# Hypnos_V3_1.net
KiCad netlist of a schematic drawn in EAGLE
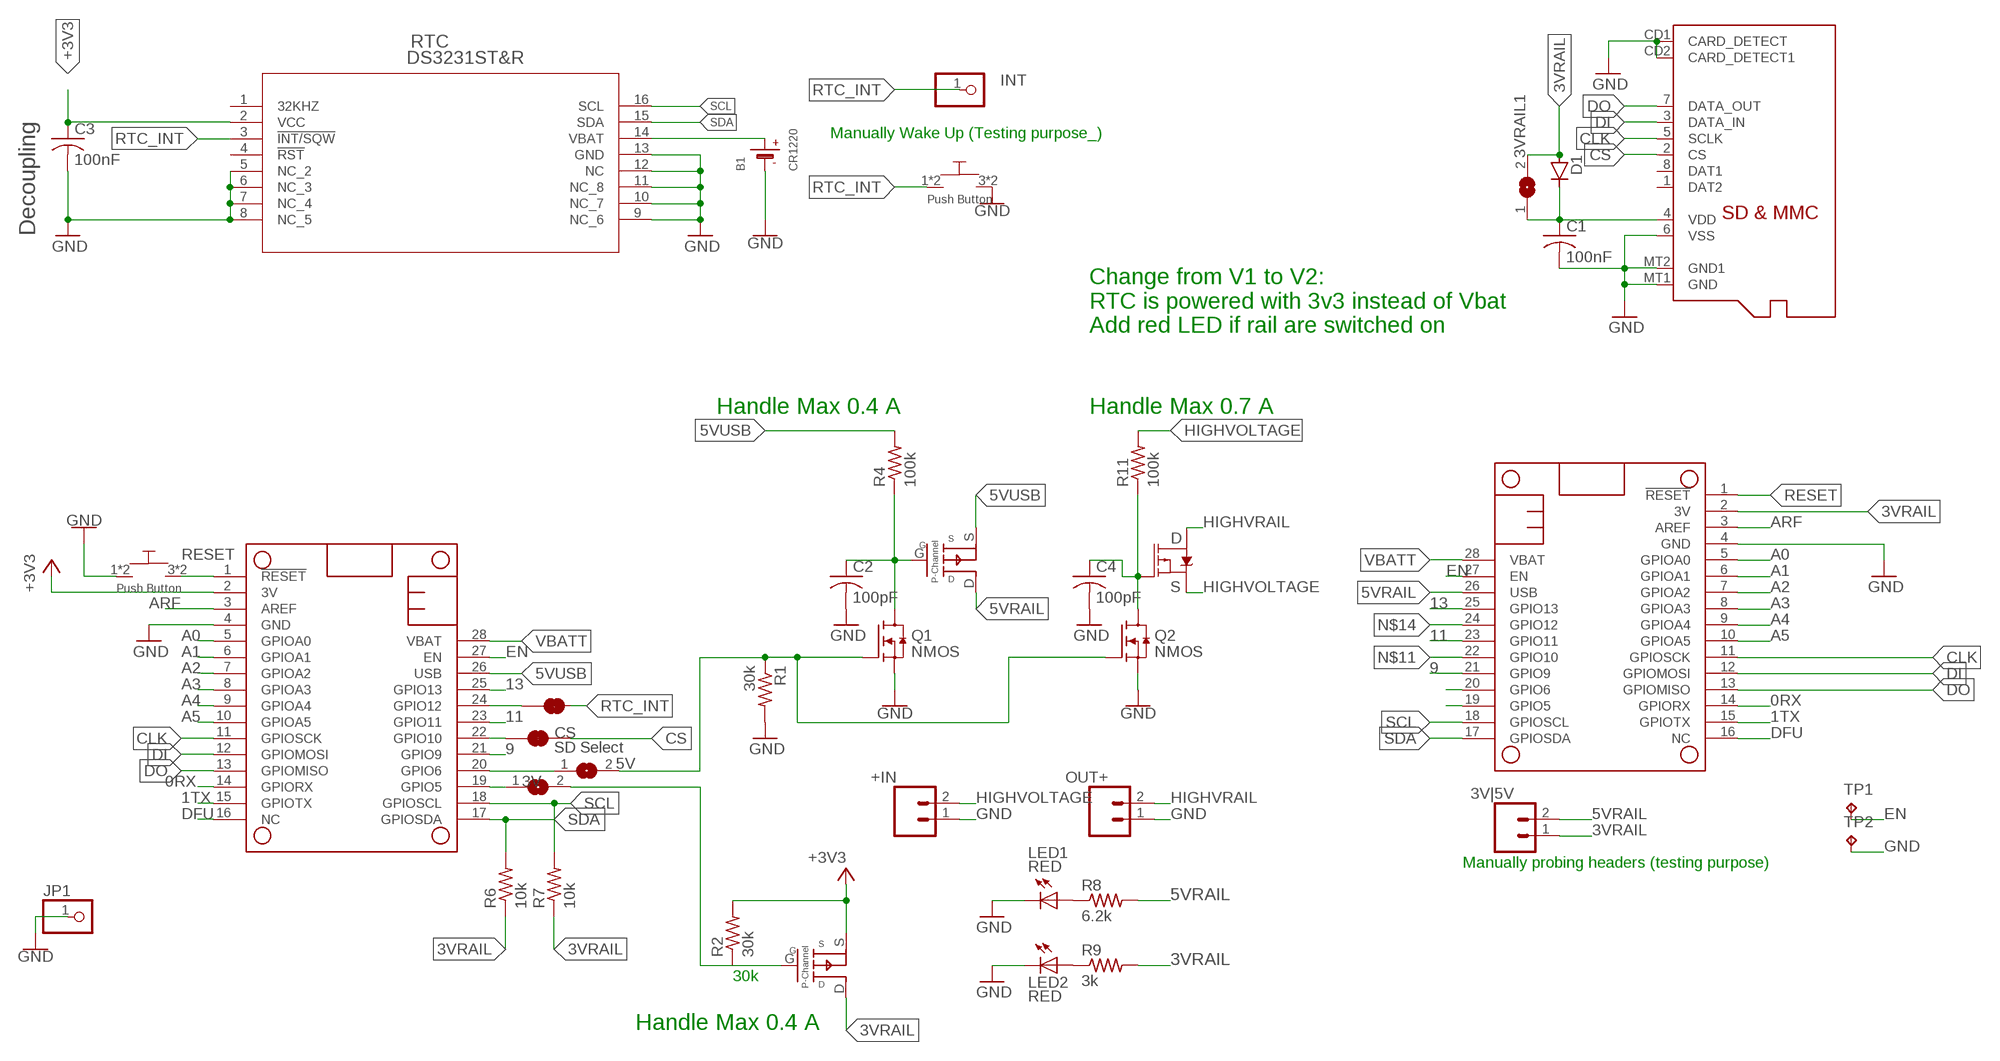
[diagram p0: schematic, sheet 1]

(export (version "E")
  (design (tool "Eeschema 10.0.6"))
  (components
    (comp (ref "+IN")
      (value "HIGHV-IN")
      (footprint "eagle-import:1X02_NO_SILK")
      (libsource (lib "eagle-import") (part "CONN_021X02_NO_SILK"))
    )
    (comp (ref "3V") (value "SJ") (footprint "eagle-import:SJ") (libsource (lib "eagle-import") (part "SJ")))
    (comp (ref "3VRAIL1")
      (value "SJ")
      (footprint "eagle-import:SJ")
      (libsource (lib "eagle-import") (part "SJ"))
    )
    (comp (ref "3V|5V")
      (value "CONN_021X02_NO_SILK")
      (footprint "eagle-import:1X02_NO_SILK")
      (libsource (lib "eagle-import") (part "CONN_021X02_NO_SILK"))
    )
    (comp (ref "5V") (value "SJ") (footprint "eagle-import:SJ") (libsource (lib "eagle-import") (part "SJ")))
    (comp (ref "B1")
      (value "CR1220")
      (footprint "eagle-import:CR1220")
      (libsource (lib "eagle-import") (part "BATTERYCR1220_SMT"))
    )
    (comp (ref "C1")
      (value "100nF")
      (footprint "eagle-import:C1206")
      (libsource (lib "eagle-import") (part "C-USC1206"))
    )
    (comp (ref "C2")
      (value "100pF")
      (footprint "eagle-import:C0805")
      (libsource (lib "eagle-import") (part "resistor_348_C-USC0805"))
    )
    (comp (ref "C3")
      (value "100nF")
      (footprint "eagle-import:C1206")
      (libsource (lib "eagle-import") (part "C-USC1206"))
    )
    (comp (ref "C4")
      (value "100pF")
      (footprint "eagle-import:C0805")
      (libsource (lib "eagle-import") (part "resistor_348_C-USC0805"))
    )
    (comp (ref "CS")
      (value "SD Select")
      (footprint "eagle-import:SMT-JUMPER_2_NC_TRACE_SILK")
      (libsource (lib "eagle-import") (part "JUMPER-SMT_2_NC_TRACE_SILK"))
    )
    (comp (ref "D1")
      (value "D-SOD123")
      (footprint "eagle-import:SOD123")
      (libsource (lib "eagle-import") (part "D-SOD123"))
    )
    (comp (ref "INT")
      (value "PINHD-1X1CB")
      (footprint "eagle-import:1X01-CLEANBIG")
      (libsource (lib "eagle-import") (part "PINHD-1X1CB"))
    )
    (comp (ref "JP1")
      (value "PINHD-1X1CB")
      (footprint "eagle-import:1X01-CLEANBIG")
      (libsource (lib "eagle-import") (part "PINHD-1X1CB"))
    )
    (comp (ref "LED1")
      (value "RED")
      (footprint "eagle-import:CHIPLED_0805")
      (libsource (lib "eagle-import") (part "LEDCHIPLED_0805"))
    )
    (comp (ref "LED2")
      (value "RED")
      (footprint "eagle-import:CHIPLED_0805")
      (libsource (lib "eagle-import") (part "LEDCHIPLED_0805"))
    )
    (comp (ref "MICROSD")
      (value "MICROSD")
      (footprint "eagle-import:MICROSD")
      (libsource (lib "eagle-import") (part "MICROSD"))
    )
    (comp (ref "MS1")
      (value "FEATHERWING")
      (footprint "eagle-import:FEATHERWING")
      (libsource (lib "eagle-import") (part "powerboard_FEATHERWING"))
    )
    (comp (ref "MS2")
      (value "FEATHERWING")
      (footprint "eagle-import:FEATHERWING")
      (libsource (lib "eagle-import") (part "FEATHERWING"))
    )
    (comp (ref "OUT+")
      (value "HIGHV-OUT")
      (footprint "eagle-import:1X02_NO_SILK")
      (libsource (lib "eagle-import") (part "CONN_021X02_NO_SILK"))
    )
    (comp (ref "PMOS1")
      (value "SSM3J3228R")
      (footprint "eagle-import:SOT-23-3")
      (libsource (lib "eagle-import") (part "SSM3J3228R"))
    )
    (comp (ref "PMOS2")
      (value "SSM3J3228R")
      (footprint "eagle-import:SOT-23-3")
      (libsource (lib "eagle-import") (part "SSM3J3228R"))
    )
    (comp (ref "PMOS3")
      (value "P-MOSFET")
      (footprint "eagle-import:SOT23-6")
      (libsource (lib "eagle-import") (part "P-MOSFET"))
    )
    (comp (ref "Q1")
      (value "NMOS")
      (footprint "eagle-import:SOT23-S")
      (libsource (lib "eagle-import") (part "NMOS"))
    )
    (comp (ref "Q2")
      (value "NMOS")
      (footprint "eagle-import:SOT23-S")
      (libsource (lib "eagle-import") (part "NMOS"))
    )
    (comp (ref "R1")
      (value "30k")
      (footprint "eagle-import:RES_1206")
      (fields
        (field (name "DIGIKEY_PART_NUMBER") "WSLP-.05TR-ND")
        (field (name "MANUFACTURER") "Vishay Dale")
        (field (name "MPN") "WSLP1206R0500FEA")
        (field (name "CREATED_BY") "PCBLayout.com")
      )
      (libsource (lib "eagle-import") (part "WSLP1206R0500FEA"))
    )
    (comp (ref "R2")
      (value "30k")
      (footprint "eagle-import:RES_1206")
      (fields
        (field (name "DIGIKEY_PART_NUMBER") "WSLP-.05TR-ND")
        (field (name "MANUFACTURER") "Vishay Dale")
        (field (name "MPN") "WSLP1206R0500FEA")
        (field (name "CREATED_BY") "PCBLayout.com")
      )
      (libsource (lib "eagle-import") (part "WSLP1206R0500FEA"))
    )
    (comp (ref "R4")
      (value "100k")
      (footprint "eagle-import:RES_1206")
      (fields
        (field (name "DIGIKEY_PART_NUMBER") "WSLP-.05TR-ND")
        (field (name "MANUFACTURER") "Vishay Dale")
        (field (name "MPN") "WSLP1206R0500FEA")
        (field (name "CREATED_BY") "PCBLayout.com")
      )
      (libsource (lib "eagle-import") (part "WSLP1206R0500FEA"))
    )
    (comp (ref "R6")
      (value "10k")
      (footprint "eagle-import:RES_1206")
      (fields
        (field (name "DIGIKEY_PART_NUMBER") "WSLP-.05TR-ND")
        (field (name "MANUFACTURER") "Vishay Dale")
        (field (name "MPN") "WSLP1206R0500FEA")
        (field (name "CREATED_BY") "PCBLayout.com")
      )
      (libsource (lib "eagle-import") (part "WSLP1206R0500FEA"))
    )
    (comp (ref "R7")
      (value "10k")
      (footprint "eagle-import:RES_1206")
      (fields
        (field (name "DIGIKEY_PART_NUMBER") "WSLP-.05TR-ND")
        (field (name "MANUFACTURER") "Vishay Dale")
        (field (name "MPN") "WSLP1206R0500FEA")
        (field (name "CREATED_BY") "PCBLayout.com")
      )
      (libsource (lib "eagle-import") (part "WSLP1206R0500FEA"))
    )
    (comp (ref "R8")
      (value "6.2k")
      (footprint "eagle-import:RES_1206")
      (fields
        (field (name "DIGIKEY_PART_NUMBER") "WSLP-.05TR-ND")
        (field (name "MANUFACTURER") "Vishay Dale")
        (field (name "MPN") "WSLP1206R0500FEA")
        (field (name "CREATED_BY") "PCBLayout.com")
      )
      (libsource (lib "eagle-import") (part "WSLP1206R0500FEA"))
    )
    (comp (ref "R9")
      (value "3k")
      (footprint "eagle-import:RES_1206")
      (fields
        (field (name "DIGIKEY_PART_NUMBER") "WSLP-.05TR-ND")
        (field (name "MANUFACTURER") "Vishay Dale")
        (field (name "MPN") "WSLP1206R0500FEA")
        (field (name "CREATED_BY") "PCBLayout.com")
      )
      (libsource (lib "eagle-import") (part "WSLP1206R0500FEA"))
    )
    (comp (ref "R11")
      (value "100k")
      (footprint "eagle-import:RES_1206")
      (fields
        (field (name "DIGIKEY_PART_NUMBER") "WSLP-.05TR-ND")
        (field (name "MANUFACTURER") "Vishay Dale")
        (field (name "MPN") "WSLP1206R0500FEA")
        (field (name "CREATED_BY") "PCBLayout.com")
      )
      (libsource (lib "eagle-import") (part "WSLP1206R0500FEA"))
    )
    (comp (ref "RTC")
      (value "DS3231ST&R")
      (footprint "eagle-import:21-0042B_16")
      (fields (field (name "MANUFACTURER_PART_NUMBER") "DS3231S#T&R"))
      (libsource (lib "eagle-import") (part "DS3231ST&R"))
    )
    (comp (ref "RTC_INT")
      (value "JUMPER-SMT_2_NC_TRACE_SILK")
      (footprint "eagle-import:SMT-JUMPER_2_NC_TRACE_SILK")
      (libsource (lib "eagle-import") (part "JUMPER-SMT_2_NC_TRACE_SILK"))
    )
    (comp (ref "TP1")
      (value "TPTP16R")
      (footprint "eagle-import:TP16R")
      (libsource (lib "eagle-import") (part "TPTP16R"))
    )
    (comp (ref "TP2")
      (value "TPTP16R")
      (footprint "eagle-import:TP16R")
      (libsource (lib "eagle-import") (part "TPTP16R"))
    )
    (comp (ref "U$1")
      (value "PUSH_BUTTON")
      (footprint "eagle-import:PUSHBUTTON_SMD")
      (libsource (lib "eagle-import") (part "PUSH_BUTTON"))
    )
    (comp (ref "U$2")
      (value "PUSH_BUTTON")
      (footprint "eagle-import:PUSHBUTTON_SMD")
      (libsource (lib "eagle-import") (part "PUSH_BUTTON"))
    )
  )
  (nets
    (net (code "1") (name "+3V3") (class "Default")
      (node (ref "C3") (pin "1") (pinfunction "1_1") (pintype "passive"))
      (node (ref "MS2") (pin "2") (pinfunction "3V_2") (pintype "power_in"))
      (node (ref "PMOS2") (pin "S") (pinfunction "S_S") (pintype "bidirectional"))
      (node (ref "R2") (pin "2") (pinfunction "2_2") (pintype "passive"))
      (node (ref "RTC") (pin "2") (pinfunction "VCC_2") (pintype "power_in"))
    )
    (net (code "2") (name "/0RX") (class "Default")
      (node (ref "MS1") (pin "14") (pinfunction "GPIORX_14") (pintype "bidirectional"))
      (node (ref "MS2") (pin "14") (pinfunction "GPIORX_14") (pintype "bidirectional"))
    )
    (net (code "3") (name "/1TX") (class "Default")
      (node (ref "MS1") (pin "15") (pinfunction "GPIOTX_15") (pintype "bidirectional"))
      (node (ref "MS2") (pin "15") (pinfunction "GPIOTX_15") (pintype "bidirectional"))
    )
    (net (code "4") (name "/9") (class "Default")
      (node (ref "MS1") (pin "21") (pinfunction "GPIO9_21") (pintype "bidirectional"))
      (node (ref "MS2") (pin "21") (pinfunction "GPIO9_21") (pintype "bidirectional"))
    )
    (net (code "5") (name "/11") (class "Default")
      (node (ref "MS1") (pin "23") (pinfunction "GPIO11_23") (pintype "bidirectional"))
      (node (ref "MS2") (pin "23") (pinfunction "GPIO11_23") (pintype "bidirectional"))
    )
    (net (code "6") (name "/13") (class "Default")
      (node (ref "MS1") (pin "25") (pinfunction "GPIO13_25") (pintype "bidirectional"))
      (node (ref "MS2") (pin "25") (pinfunction "GPIO13_25") (pintype "bidirectional"))
    )
    (net (code "7") (name "/A0") (class "Default")
      (node (ref "MS1") (pin "5") (pinfunction "GPIOA0_5") (pintype "bidirectional"))
      (node (ref "MS2") (pin "5") (pinfunction "GPIOA0_5") (pintype "bidirectional"))
    )
    (net (code "8") (name "/A1") (class "Default")
      (node (ref "MS1") (pin "6") (pinfunction "GPIOA1_6") (pintype "bidirectional"))
      (node (ref "MS2") (pin "6") (pinfunction "GPIOA1_6") (pintype "bidirectional"))
    )
    (net (code "9") (name "/A2") (class "Default")
      (node (ref "MS1") (pin "7") (pinfunction "GPIOA2_7") (pintype "bidirectional"))
      (node (ref "MS2") (pin "7") (pinfunction "GPIOA2_7") (pintype "bidirectional"))
    )
    (net (code "10") (name "/A3") (class "Default")
      (node (ref "MS1") (pin "8") (pinfunction "GPIOA3_8") (pintype "bidirectional"))
      (node (ref "MS2") (pin "8") (pinfunction "GPIOA3_8") (pintype "bidirectional"))
    )
    (net (code "11") (name "/A4") (class "Default")
      (node (ref "MS1") (pin "9") (pinfunction "GPIOA4_9") (pintype "bidirectional"))
      (node (ref "MS2") (pin "9") (pinfunction "GPIOA4_9") (pintype "bidirectional"))
    )
    (net (code "12") (name "/A5") (class "Default")
      (node (ref "MS1") (pin "10") (pinfunction "GPIOA5_10") (pintype "bidirectional"))
      (node (ref "MS2") (pin "10") (pinfunction "GPIOA5_10") (pintype "bidirectional"))
    )
    (net (code "13") (name "/ARF") (class "Default")
      (node (ref "MS1") (pin "3") (pinfunction "AREF_3") (pintype "passive"))
      (node (ref "MS2") (pin "3") (pinfunction "AREF_3") (pintype "passive"))
    )
    (net (code "14") (name "/DFU") (class "Default")
      (node (ref "MS1") (pin "16") (pinfunction "NC_16") (pintype "passive"))
      (node (ref "MS2") (pin "16") (pinfunction "NC_16") (pintype "passive"))
    )
    (net (code "15") (name "/EN") (class "Default")
      (node (ref "MS1") (pin "27") (pinfunction "EN_27") (pintype "passive"))
      (node (ref "MS2") (pin "27") (pinfunction "EN_27") (pintype "passive"))
      (node (ref "TP1") (pin "TP") (pinfunction "TP_TP") (pintype "input"))
    )
    (net (code "16") (name "/HIGHVRAIL") (class "Default")
      (node (ref "OUT+") (pin "2") (pinfunction "2_2") (pintype "passive"))
      (node (ref "PMOS3") (pin "1") (pinfunction "D_1") (pintype "bidirectional"))
      (node (ref "PMOS3") (pin "2") (pinfunction "D_2") (pintype "bidirectional"))
      (node (ref "PMOS3") (pin "5") (pinfunction "D_5") (pintype "bidirectional"))
      (node (ref "PMOS3") (pin "6") (pinfunction "D_6") (pintype "bidirectional"))
    )
    (net (code "17") (name "3VRAIL") (class "Default")
      (node (ref "3VRAIL1") (pin "2") (pinfunction "2_2") (pintype "passive"))
      (node (ref "3V|5V") (pin "1") (pinfunction "1_1") (pintype "passive"))
      (node (ref "D1") (pin "2") (pinfunction "A_2") (pintype "passive"))
      (node (ref "MS1") (pin "2") (pinfunction "3V_2") (pintype "power_in"))
      (node (ref "PMOS2") (pin "D") (pinfunction "D_D") (pintype "bidirectional"))
      (node (ref "R6") (pin "1") (pinfunction "1_1") (pintype "passive"))
      (node (ref "R7") (pin "1") (pinfunction "1_1") (pintype "passive"))
      (node (ref "R9") (pin "2") (pinfunction "2_2") (pintype "passive"))
    )
    (net (code "18") (name "5VRAIL") (class "Default")
      (node (ref "3V|5V") (pin "2") (pinfunction "2_2") (pintype "passive"))
      (node (ref "MS1") (pin "26") (pinfunction "USB_26") (pintype "power_in"))
      (node (ref "PMOS1") (pin "D") (pinfunction "D_D") (pintype "bidirectional"))
      (node (ref "R8") (pin "2") (pinfunction "2_2") (pintype "passive"))
    )
    (net (code "19") (name "5VUSB") (class "Default")
      (node (ref "MS2") (pin "26") (pinfunction "USB_26") (pintype "power_in"))
      (node (ref "PMOS1") (pin "S") (pinfunction "S_S") (pintype "bidirectional"))
      (node (ref "R4") (pin "2") (pinfunction "2_2") (pintype "passive"))
    )
    (net (code "20") (name "CLK") (class "Default")
      (node (ref "MICROSD") (pin "5") (pinfunction "SCLK_5") (pintype "input"))
      (node (ref "MS1") (pin "11") (pinfunction "GPIOSCK_11") (pintype "bidirectional"))
      (node (ref "MS2") (pin "11") (pinfunction "GPIOSCK_11") (pintype "bidirectional"))
    )
    (net (code "21") (name "CS") (class "Default")
      (node (ref "CS") (pin "2") (pinfunction "2_2") (pintype "passive"))
      (node (ref "MICROSD") (pin "2") (pinfunction "CS_2") (pintype "input"))
    )
    (net (code "22") (name "DI") (class "Default")
      (node (ref "MICROSD") (pin "3") (pinfunction "DATA_IN_3") (pintype "input"))
      (node (ref "MS1") (pin "12") (pinfunction "GPIOMOSI_12") (pintype "bidirectional"))
      (node (ref "MS2") (pin "12") (pinfunction "GPIOMOSI_12") (pintype "bidirectional"))
    )
    (net (code "23") (name "DO") (class "Default")
      (node (ref "MICROSD") (pin "7") (pinfunction "DATA_OUT_7") (pintype "output"))
      (node (ref "MS1") (pin "13") (pinfunction "GPIOMISO_13") (pintype "bidirectional"))
      (node (ref "MS2") (pin "13") (pinfunction "GPIOMISO_13") (pintype "bidirectional"))
    )
    (net (code "24") (name "GND") (class "Default")
      (node (ref "+IN") (pin "1") (pinfunction "1_1") (pintype "passive"))
      (node (ref "B1") (pin "-") (pinfunction "-_-") (pintype "passive"))
      (node (ref "C1") (pin "2") (pinfunction "2_2") (pintype "passive"))
      (node (ref "C2") (pin "2") (pinfunction "2_2") (pintype "passive"))
      (node (ref "C3") (pin "2") (pinfunction "2_2") (pintype "passive"))
      (node (ref "C4") (pin "2") (pinfunction "2_2") (pintype "passive"))
      (node (ref "JP1") (pin "1") (pinfunction "1_1") (pintype "passive"))
      (node (ref "LED1") (pin "C") (pinfunction "C_C") (pintype "passive"))
      (node (ref "LED2") (pin "C") (pinfunction "C_C") (pintype "passive"))
      (node (ref "MICROSD") (pin "6") (pinfunction "VSS_6") (pintype "power_in"))
      (node (ref "MICROSD") (pin "CD1") (pinfunction "CARD_DETECT_CD1") (pintype "passive"))
      (node (ref "MICROSD") (pin "CD2") (pinfunction "CARD_DETECT1_CD2") (pintype "passive"))
      (node (ref "MICROSD") (pin "MT1") (pinfunction "GND_MT1") (pintype "power_in"))
      (node (ref "MICROSD") (pin "MT2") (pinfunction "GND1_MT2") (pintype "power_in"))
      (node (ref "MS1") (pin "4") (pinfunction "GND_4") (pintype "power_in"))
      (node (ref "MS2") (pin "4") (pinfunction "GND_4") (pintype "power_in"))
      (node (ref "OUT+") (pin "1") (pinfunction "1_1") (pintype "passive"))
      (node (ref "Q1") (pin "2") (pinfunction "S_2") (pintype "passive"))
      (node (ref "Q2") (pin "2") (pinfunction "S_2") (pintype "passive"))
      (node (ref "R1") (pin "2") (pinfunction "2_2") (pintype "passive"))
      (node (ref "RTC") (pin "10") (pinfunction "NC_7_10") (pintype "passive"))
      (node (ref "RTC") (pin "11") (pinfunction "NC_8_11") (pintype "passive"))
      (node (ref "RTC") (pin "12") (pinfunction "NC_12") (pintype "passive"))
      (node (ref "RTC") (pin "13") (pinfunction "GND_13") (pintype "power_in"))
      (node (ref "RTC") (pin "5") (pinfunction "NC_2_5") (pintype "passive"))
      (node (ref "RTC") (pin "6") (pinfunction "NC_3_6") (pintype "passive"))
      (node (ref "RTC") (pin "7") (pinfunction "NC_4_7") (pintype "passive"))
      (node (ref "RTC") (pin "8") (pinfunction "NC_5_8") (pintype "passive"))
      (node (ref "RTC") (pin "9") (pinfunction "NC_6_9") (pintype "passive"))
      (node (ref "TP2") (pin "TP") (pinfunction "TP_TP") (pintype "input"))
      (node (ref "U$1") (pin "1") (pinfunction "P$1_1") (pintype "bidirectional"))
      (node (ref "U$1") (pin "2") (pinfunction "P$1_2") (pintype "bidirectional"))
      (node (ref "U$2") (pin "3") (pinfunction "P$2_3") (pintype "bidirectional"))
      (node (ref "U$2") (pin "4") (pinfunction "P$2_4") (pintype "bidirectional"))
    )
    (net (code "25") (name "HIGHVOLTAGE") (class "Default")
      (node (ref "+IN") (pin "2") (pinfunction "2_2") (pintype "passive"))
      (node (ref "PMOS3") (pin "4") (pinfunction "S_4") (pintype "bidirectional"))
      (node (ref "R11") (pin "2") (pinfunction "2_2") (pintype "passive"))
    )
    (net (code "26") (name "N$11") (class "Default")
      (node (ref "CS") (pin "1") (pinfunction "1_1") (pintype "passive"))
      (node (ref "MS1") (pin "22") (pinfunction "GPIO10_22") (pintype "bidirectional"))
      (node (ref "MS2") (pin "22") (pinfunction "GPIO10_22") (pintype "bidirectional"))
    )
    (net (code "27") (name "N$14") (class "Default")
      (node (ref "MS1") (pin "24") (pinfunction "GPIO12_24") (pintype "bidirectional"))
      (node (ref "MS2") (pin "24") (pinfunction "GPIO12_24") (pintype "bidirectional"))
      (node (ref "RTC_INT") (pin "1") (pinfunction "1_1") (pintype "passive"))
    )
    (net (code "28") (name "Net-(3V-Pad2)") (class "Default")
      (node (ref "3V") (pin "2") (pinfunction "2_2") (pintype "passive"))
      (node (ref "PMOS2") (pin "G") (pinfunction "G_G") (pintype "bidirectional"))
      (node (ref "R2") (pin "1") (pinfunction "1_1") (pintype "passive"))
    )
    (net (code "29") (name "Net-(B1-+)") (class "Default")
      (node (ref "B1") (pin "+$1") (pinfunction "+_+$1") (pintype "passive"))
      (node (ref "RTC") (pin "14") (pinfunction "VBAT_14") (pintype "power_in"))
    )
    (net (code "30") (name "Net-(D1-C)") (class "Default")
      (node (ref "3VRAIL1") (pin "1") (pinfunction "1_1") (pintype "passive"))
      (node (ref "C1") (pin "1") (pinfunction "1_1") (pintype "passive"))
      (node (ref "D1") (pin "1") (pinfunction "C_1") (pintype "passive"))
      (node (ref "MICROSD") (pin "4") (pinfunction "VDD_4") (pintype "power_in"))
    )
    (net (code "31") (name "Net-(LED1-PadA)") (class "Default")
      (node (ref "LED1") (pin "A") (pinfunction "A_A") (pintype "passive"))
      (node (ref "R8") (pin "1") (pinfunction "1_1") (pintype "passive"))
    )
    (net (code "32") (name "Net-(LED2-PadA)") (class "Default")
      (node (ref "LED2") (pin "A") (pinfunction "A_A") (pintype "passive"))
      (node (ref "R9") (pin "1") (pinfunction "1_1") (pintype "passive"))
    )
    (net (code "33") (name "Net-(MS2-GPIO5)") (class "Default")
      (node (ref "3V") (pin "1") (pinfunction "1_1") (pintype "passive"))
      (node (ref "MS2") (pin "19") (pinfunction "GPIO5_19") (pintype "bidirectional"))
    )
    (net (code "34") (name "Net-(MS2-GPIO6)") (class "Default")
      (node (ref "5V") (pin "1") (pinfunction "1_1") (pintype "passive"))
      (node (ref "MS2") (pin "20") (pinfunction "GPIO6_20") (pintype "bidirectional"))
    )
    (net (code "35") (name "Net-(PMOS3-G)") (class "Default")
      (node (ref "C4") (pin "1") (pinfunction "1_1") (pintype "passive"))
      (node (ref "PMOS3") (pin "3") (pinfunction "G_3") (pintype "bidirectional"))
      (node (ref "Q2") (pin "3") (pinfunction "D_3") (pintype "passive"))
      (node (ref "R11") (pin "1") (pinfunction "1_1") (pintype "passive"))
    )
    (net (code "36") (name "Net-(Q1-D)") (class "Default")
      (node (ref "C2") (pin "1") (pinfunction "1_1") (pintype "passive"))
      (node (ref "PMOS1") (pin "G") (pinfunction "G_G") (pintype "bidirectional"))
      (node (ref "Q1") (pin "3") (pinfunction "D_3") (pintype "passive"))
      (node (ref "R4") (pin "1") (pinfunction "1_1") (pintype "passive"))
    )
    (net (code "37") (name "Net-(Q1-G)") (class "Default")
      (node (ref "5V") (pin "2") (pinfunction "2_2") (pintype "passive"))
      (node (ref "Q1") (pin "1") (pinfunction "G_1") (pintype "passive"))
      (node (ref "Q2") (pin "1") (pinfunction "G_1") (pintype "passive"))
      (node (ref "R1") (pin "1") (pinfunction "1_1") (pintype "passive"))
    )
    (net (code "38") (name "RESET") (class "Default")
      (node (ref "MS1") (pin "1") (pinfunction "~{RESET}_1") (pintype "input"))
      (node (ref "MS2") (pin "1") (pinfunction "~{RESET}_1") (pintype "input"))
      (node (ref "U$1") (pin "3") (pinfunction "P$2_3") (pintype "bidirectional"))
      (node (ref "U$1") (pin "4") (pinfunction "P$2_4") (pintype "bidirectional"))
    )
    (net (code "39") (name "RTC_INT") (class "Default")
      (node (ref "INT") (pin "1") (pinfunction "1_1") (pintype "passive"))
      (node (ref "RTC") (pin "3") (pinfunction "~{INT/SQW}_3") (pintype "passive"))
      (node (ref "RTC_INT") (pin "2") (pinfunction "2_2") (pintype "passive"))
      (node (ref "U$2") (pin "1") (pinfunction "P$1_1") (pintype "bidirectional"))
      (node (ref "U$2") (pin "2") (pinfunction "P$1_2") (pintype "bidirectional"))
    )
    (net (code "40") (name "SCL") (class "Default")
      (node (ref "MS1") (pin "18") (pinfunction "GPIOSCL_18") (pintype "bidirectional"))
      (node (ref "MS2") (pin "18") (pinfunction "GPIOSCL_18") (pintype "bidirectional"))
      (node (ref "R7") (pin "2") (pinfunction "2_2") (pintype "passive"))
      (node (ref "RTC") (pin "16") (pinfunction "SCL_16") (pintype "passive"))
    )
    (net (code "41") (name "SDA") (class "Default")
      (node (ref "MS1") (pin "17") (pinfunction "GPIOSDA_17") (pintype "bidirectional"))
      (node (ref "MS2") (pin "17") (pinfunction "GPIOSDA_17") (pintype "bidirectional"))
      (node (ref "R6") (pin "2") (pinfunction "2_2") (pintype "passive"))
      (node (ref "RTC") (pin "15") (pinfunction "SDA_15") (pintype "passive"))
    )
    (net (code "42") (name "VBATT") (class "Default")
      (node (ref "MS1") (pin "28") (pinfunction "VBAT_28") (pintype "power_in"))
      (node (ref "MS2") (pin "28") (pinfunction "VBAT_28") (pintype "power_in"))
    )
    (net (code "43") (name "unconnected-(MICROSD-DAT1-Pad8)") (class "Default")
      (node (ref "MICROSD") (pin "8") (pinfunction "DAT1_8") (pintype "bidirectional"))
    )
    (net (code "44") (name "unconnected-(MICROSD-DAT2-Pad1)") (class "Default")
      (node (ref "MICROSD") (pin "1") (pinfunction "DAT2_1") (pintype "bidirectional"))
    )
    (net (code "45") (name "unconnected-(MS1-GPIO5-Pad19)") (class "Default")
      (node (ref "MS1") (pin "19") (pinfunction "GPIO5_19") (pintype "bidirectional"))
    )
    (net (code "46") (name "unconnected-(MS1-GPIO6-Pad20)") (class "Default")
      (node (ref "MS1") (pin "20") (pinfunction "GPIO6_20") (pintype "bidirectional"))
    )
    (net (code "47") (name "unconnected-(RTC-32KHZ-Pad1)") (class "Default")
      (node (ref "RTC") (pin "1") (pinfunction "32KHZ_1") (pintype "passive"))
    )
    (net (code "48") (name "unconnected-(RTC-~{RST}-Pad4)") (class "Default")
      (node (ref "RTC") (pin "4") (pinfunction "~{RST}_4") (pintype "passive"))
    )
  )
)
